# gerbang_f2.net
KiCad netlist of a schematic drawn in EAGLE
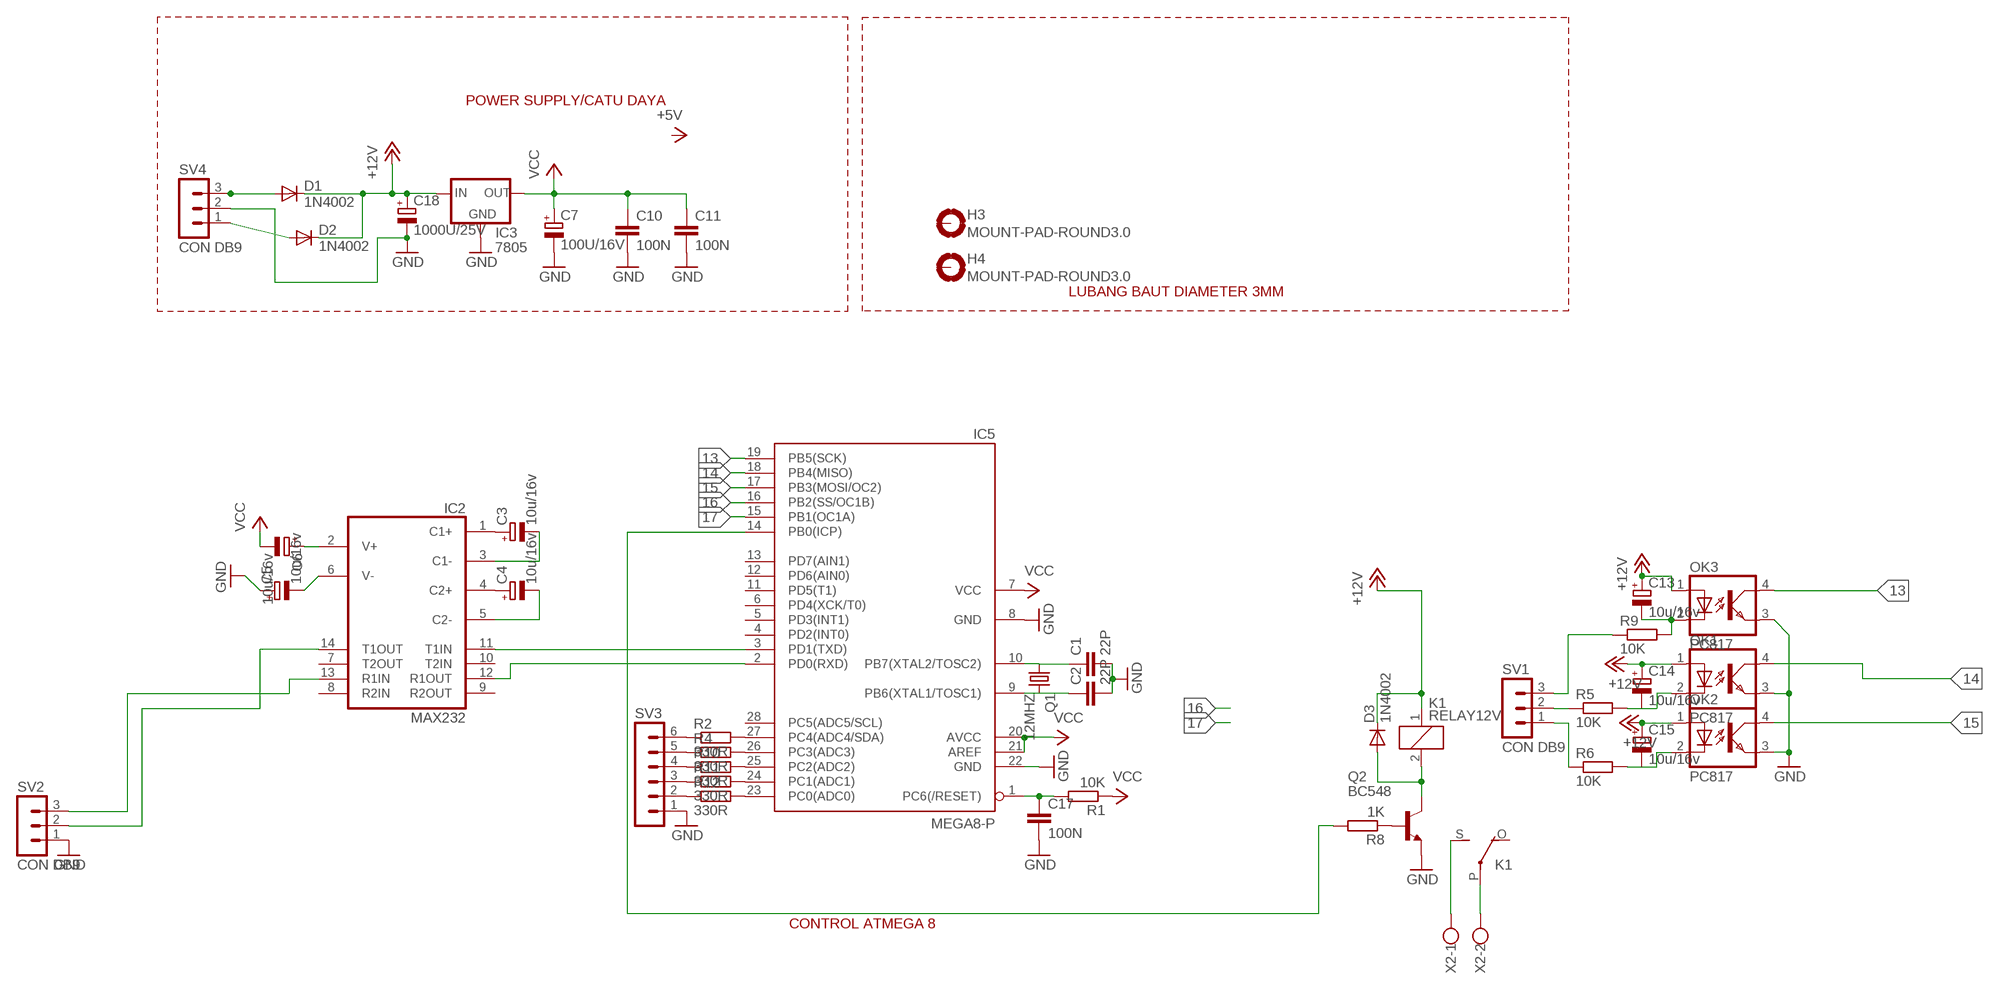
[diagram p0: schematic, sheet 1]

(export (version "E")
  (design (tool "Eeschema 10.0.6"))
  (components
    (comp (ref "C1")
      (value "22P")
      (footprint "eagle-import:C025-025X050")
      (libsource (lib "eagle-import") (part "C-EU025-025X050"))
    )
    (comp (ref "C2")
      (value "22P")
      (footprint "eagle-import:C025-025X050")
      (libsource (lib "eagle-import") (part "C-EU025-025X050"))
    )
    (comp (ref "C3")
      (value "10u/16v")
      (footprint "eagle-import:E2,5-6")
      (libsource (lib "eagle-import") (part "resistor_CPOL-EUE2.5-6"))
    )
    (comp (ref "C4")
      (value "10u/16v")
      (footprint "eagle-import:E2,5-6")
      (libsource (lib "eagle-import") (part "resistor_CPOL-EUE2.5-6"))
    )
    (comp (ref "C5")
      (value "10u/16v")
      (footprint "eagle-import:E2,5-6")
      (libsource (lib "eagle-import") (part "resistor_CPOL-EUE2.5-6"))
    )
    (comp (ref "C6")
      (value "10u/16v")
      (footprint "eagle-import:E2,5-6")
      (libsource (lib "eagle-import") (part "resistor_CPOL-EUE2.5-6"))
    )
    (comp (ref "C7")
      (value "100U/16V")
      (footprint "eagle-import:E2,5-6")
      (libsource (lib "eagle-import") (part "resistor_CPOL-EUE2.5-6"))
    )
    (comp (ref "C10")
      (value "100N")
      (footprint "eagle-import:C025-025X050")
      (libsource (lib "eagle-import") (part "C-EU025-025X050"))
    )
    (comp (ref "C11")
      (value "100N")
      (footprint "eagle-import:C025-025X050")
      (libsource (lib "eagle-import") (part "C-EU025-025X050"))
    )
    (comp (ref "C13")
      (value "10u/16v")
      (footprint "eagle-import:E2,5-6")
      (libsource (lib "eagle-import") (part "resistor_CPOL-EUE2.5-6"))
    )
    (comp (ref "C14")
      (value "10u/16v")
      (footprint "eagle-import:E2,5-6")
      (libsource (lib "eagle-import") (part "resistor_CPOL-EUE2.5-6"))
    )
    (comp (ref "C15")
      (value "10u/16v")
      (footprint "eagle-import:E2,5-6")
      (libsource (lib "eagle-import") (part "resistor_CPOL-EUE2.5-6"))
    )
    (comp (ref "C17")
      (value "100N")
      (footprint "eagle-import:C025-025X050")
      (libsource (lib "eagle-import") (part "C-EU025-025X050"))
    )
    (comp (ref "C18")
      (value "1000U/25V")
      (footprint "eagle-import:E5-8,5")
      (libsource (lib "eagle-import") (part "CPOL-EUE5-8.5"))
    )
    (comp (ref "D1")
      (value "1N4002")
      (footprint "eagle-import:DO35-10")
      (libsource (lib "eagle-import") (part "1N4148DO35-10"))
    )
    (comp (ref "D2")
      (value "1N4002")
      (footprint "eagle-import:DO35-10")
      (libsource (lib "eagle-import") (part "1N4148DO35-10"))
    )
    (comp (ref "D3")
      (value "1N4002")
      (footprint "eagle-import:DO35-10")
      (libsource (lib "eagle-import") (part "1N4148DO35-10"))
    )
    (comp (ref "H3")
      (value "MOUNT-PAD-ROUND3.0")
      (footprint "eagle-import:3,0-PAD")
      (libsource (lib "eagle-import") (part "MOUNT-PAD-ROUND3.0"))
    )
    (comp (ref "H4")
      (value "MOUNT-PAD-ROUND3.0")
      (footprint "eagle-import:3,0-PAD")
      (libsource (lib "eagle-import") (part "MOUNT-PAD-ROUND3.0"))
    )
    (comp (ref "IC2")
      (value "MAX232")
      (footprint "eagle-import:DIL16")
      (fields (field (name "MF") "MAXIM") (field (name "MPN") "MAX232ACPE+"))
      (libsource (lib "eagle-import") (part "MAX232"))
    )
    (comp (ref "IC3")
      (value "7805")
      (footprint "eagle-import:78XXS")
      (libsource (lib "eagle-import") (part "78XXS"))
    )
    (comp (ref "IC5")
      (value "MEGA8-P")
      (footprint "eagle-import:DIL28-3")
      (libsource (lib "eagle-import") (part "MEGA8-P"))
    )
    (comp (ref "K1")
      (value "RELAY12V")
      (footprint "eagle-import:ZF112")
      (libsource (lib "eagle-import") (part "ZF112"))
    )
    (comp (ref "OK1")
      (value "PC817")
      (footprint "eagle-import:DIL04")
      (fields (field (name "MPN") "PC817X4J000F"))
      (libsource (lib "eagle-import") (part "PC817"))
    )
    (comp (ref "OK2")
      (value "PC817")
      (footprint "eagle-import:DIL04")
      (fields (field (name "MPN") "PC817X4J000F"))
      (libsource (lib "eagle-import") (part "PC817"))
    )
    (comp (ref "OK3")
      (value "PC817")
      (footprint "eagle-import:DIL04")
      (fields (field (name "MPN") "PC817X4J000F"))
      (libsource (lib "eagle-import") (part "PC817"))
    )
    (comp (ref "Q1")
      (value "12MHZ")
      (footprint "eagle-import:HC49U-V")
      (libsource (lib "eagle-import") (part "CRYSTALHC49U-V"))
    )
    (comp (ref "Q2")
      (value "BC548")
      (footprint "eagle-import:TO92-EBC")
      (libsource (lib "eagle-import") (part "BC548"))
    )
    (comp (ref "R1")
      (value "10K")
      (footprint "eagle-import:0207_10")
      (libsource (lib "eagle-import") (part "resistor_R-EU_0207/10"))
    )
    (comp (ref "R2")
      (value "330R")
      (footprint "eagle-import:0204V")
      (libsource (lib "eagle-import") (part "R-EU_0204/2V"))
    )
    (comp (ref "R4")
      (value "330R")
      (footprint "eagle-import:0204V")
      (libsource (lib "eagle-import") (part "R-EU_0204/2V"))
    )
    (comp (ref "R5")
      (value "10K")
      (footprint "eagle-import:0204V")
      (libsource (lib "eagle-import") (part "R-EU_0204/2V"))
    )
    (comp (ref "R6")
      (value "10K")
      (footprint "eagle-import:0204V")
      (libsource (lib "eagle-import") (part "R-EU_0204/2V"))
    )
    (comp (ref "R8")
      (value "1K")
      (footprint "eagle-import:0207_10")
      (libsource (lib "eagle-import") (part "resistor_R-EU_0207/10"))
    )
    (comp (ref "R9")
      (value "10K")
      (footprint "eagle-import:0204V")
      (libsource (lib "eagle-import") (part "R-EU_0204/2V"))
    )
    (comp (ref "R10")
      (value "330R")
      (footprint "eagle-import:0204V")
      (libsource (lib "eagle-import") (part "R-EU_0204/2V"))
    )
    (comp (ref "R11")
      (value "330R")
      (footprint "eagle-import:0204V")
      (libsource (lib "eagle-import") (part "R-EU_0204/2V"))
    )
    (comp (ref "R12")
      (value "330R")
      (footprint "eagle-import:0204V")
      (libsource (lib "eagle-import") (part "R-EU_0204/2V"))
    )
    (comp (ref "SV1")
      (value "CON DB9")
      (footprint "eagle-import:MA03-1")
      (libsource (lib "eagle-import") (part "MA03-1"))
    )
    (comp (ref "SV2")
      (value "CON DB9")
      (footprint "eagle-import:MA03-1")
      (libsource (lib "eagle-import") (part "MA03-1"))
    )
    (comp (ref "SV3")
      (value "MA06-1")
      (footprint "eagle-import:MA06-1")
      (libsource (lib "eagle-import") (part "MA06-1"))
    )
    (comp (ref "SV4")
      (value "CON DB9")
      (footprint "eagle-import:MA03-1")
      (libsource (lib "eagle-import") (part "MA03-1"))
    )
    (comp (ref "X2")
      (value "W237-102")
      (footprint "eagle-import:W237-102")
      (fields (field (name "MPN") "237-102"))
      (libsource (lib "eagle-import") (part "W237-102"))
    )
  )
  (nets
    (net (code "2") (name "+12V") (class "Default")
      (node (ref "C13") (pin "+") (pinfunction "+_+") (pintype "passive"))
      (node (ref "C14") (pin "+") (pinfunction "+_+") (pintype "passive"))
      (node (ref "C15") (pin "+") (pinfunction "+_+") (pintype "passive"))
      (node (ref "C18") (pin "+") (pinfunction "+_+") (pintype "passive"))
      (node (ref "D1") (pin "C") (pinfunction "C_C") (pintype "passive"))
      (node (ref "D2") (pin "C") (pinfunction "C_C") (pintype "passive"))
      (node (ref "D3") (pin "C") (pinfunction "C_C") (pintype "passive"))
      (node (ref "IC3") (pin "IN") (pinfunction "IN_IN") (pintype "input"))
      (node (ref "K1") (pin "1") (pinfunction "1_1") (pintype "passive"))
      (node (ref "OK1") (pin "1") (pinfunction "A_1") (pintype "passive"))
      (node (ref "OK2") (pin "1") (pinfunction "A_1") (pintype "passive"))
      (node (ref "OK3") (pin "1") (pinfunction "A_1") (pintype "passive"))
    )
    (net (code "3") (name "13") (class "Default")
      (node (ref "IC5") (pin "19") (pinfunction "PB5(SCK)_19") (pintype "bidirectional"))
      (node (ref "OK3") (pin "4") (pinfunction "COL_4") (pintype "passive"))
    )
    (net (code "4") (name "14") (class "Default")
      (node (ref "IC5") (pin "18") (pinfunction "PB4(MISO)_18") (pintype "bidirectional"))
      (node (ref "OK1") (pin "4") (pinfunction "COL_4") (pintype "passive"))
    )
    (net (code "5") (name "15") (class "Default")
      (node (ref "IC5") (pin "17") (pinfunction "PB3(MOSI/OC2)_17") (pintype "bidirectional"))
      (node (ref "OK2") (pin "4") (pinfunction "COL_4") (pintype "passive"))
    )
    (net (code "6") (name "16") (class "Default")
      (node (ref "IC5") (pin "16") (pinfunction "PB2(SS/OC1B)_16") (pintype "bidirectional"))
    )
    (net (code "7") (name "17") (class "Default")
      (node (ref "IC5") (pin "15") (pinfunction "PB1(OC1A)_15") (pintype "bidirectional"))
    )
    (net (code "8") (name "GND") (class "Default")
      (node (ref "C1") (pin "2") (pinfunction "2_2") (pintype "passive"))
      (node (ref "C10") (pin "2") (pinfunction "2_2") (pintype "passive"))
      (node (ref "C11") (pin "2") (pinfunction "2_2") (pintype "passive"))
      (node (ref "C17") (pin "2") (pinfunction "2_2") (pintype "passive"))
      (node (ref "C18") (pin "-") (pinfunction "-_-") (pintype "passive"))
      (node (ref "C2") (pin "2") (pinfunction "2_2") (pintype "passive"))
      (node (ref "C5") (pin "+") (pinfunction "+_+") (pintype "passive"))
      (node (ref "C7") (pin "-") (pinfunction "-_-") (pintype "passive"))
      (node (ref "IC3") (pin "GND") (pinfunction "GND_GND") (pintype "input"))
      (node (ref "IC5") (pin "22") (pinfunction "GND_22") (pintype "power_in"))
      (node (ref "IC5") (pin "8") (pinfunction "GND_8") (pintype "power_in"))
      (node (ref "OK1") (pin "3") (pinfunction "EMIT_3") (pintype "passive"))
      (node (ref "OK2") (pin "3") (pinfunction "EMIT_3") (pintype "passive"))
      (node (ref "OK3") (pin "3") (pinfunction "EMIT_3") (pintype "passive"))
      (node (ref "Q2") (pin "E") (pinfunction "E_E") (pintype "passive"))
      (node (ref "SV2") (pin "1") (pinfunction "1_1") (pintype "passive"))
      (node (ref "SV3") (pin "1") (pinfunction "1_1") (pintype "passive"))
      (node (ref "SV4") (pin "2") (pinfunction "2_2") (pintype "passive"))
    )
    (net (code "9") (name "Net-(D1-PadA)") (class "Default")
      (node (ref "D1") (pin "A") (pinfunction "A_A") (pintype "passive"))
      (node (ref "SV4") (pin "3") (pinfunction "3_3") (pintype "passive"))
    )
    (net (code "10") (name "Net-(D2-PadA)") (class "Default")
      (node (ref "D2") (pin "A") (pinfunction "A_A") (pintype "passive"))
      (node (ref "SV4") (pin "1") (pinfunction "1_1") (pintype "passive"))
    )
    (net (code "11") (name "Net-(D3-PadA)") (class "Default")
      (node (ref "D3") (pin "A") (pinfunction "A_A") (pintype "passive"))
      (node (ref "K1") (pin "2") (pinfunction "2_2") (pintype "passive"))
      (node (ref "Q2") (pin "C") (pinfunction "C_C") (pintype "passive"))
    )
    (net (code "12") (name "Net-(IC2A-C1+)") (class "Default")
      (node (ref "C3") (pin "+") (pinfunction "+_+") (pintype "passive"))
      (node (ref "IC2") (pin "1") (pinfunction "C1+_1") (pintype "bidirectional"))
    )
    (net (code "13") (name "Net-(IC2A-C1-)") (class "Default")
      (node (ref "C3") (pin "-") (pinfunction "-_-") (pintype "passive"))
      (node (ref "IC2") (pin "3") (pinfunction "C1-_3") (pintype "bidirectional"))
    )
    (net (code "14") (name "Net-(IC2A-C2+)") (class "Default")
      (node (ref "C4") (pin "+") (pinfunction "+_+") (pintype "passive"))
      (node (ref "IC2") (pin "4") (pinfunction "C2+_4") (pintype "bidirectional"))
    )
    (net (code "15") (name "Net-(IC2A-C2-)") (class "Default")
      (node (ref "C4") (pin "-") (pinfunction "-_-") (pintype "passive"))
      (node (ref "IC2") (pin "5") (pinfunction "C2-_5") (pintype "bidirectional"))
    )
    (net (code "16") (name "Net-(IC2A-R1IN)") (class "Default")
      (node (ref "IC2") (pin "13") (pinfunction "R1IN_13") (pintype "input"))
      (node (ref "SV2") (pin "3") (pinfunction "3_3") (pintype "passive"))
    )
    (net (code "17") (name "Net-(IC2A-R1OUT)") (class "Default")
      (node (ref "IC2") (pin "12") (pinfunction "R1OUT_12") (pintype "output"))
      (node (ref "IC5") (pin "2") (pinfunction "PD0(RXD)_2") (pintype "bidirectional"))
    )
    (net (code "18") (name "Net-(IC2A-T1IN)") (class "Default")
      (node (ref "IC2") (pin "11") (pinfunction "T1IN_11") (pintype "input"))
      (node (ref "IC5") (pin "3") (pinfunction "PD1(TXD)_3") (pintype "bidirectional"))
    )
    (net (code "19") (name "Net-(IC2A-T1OUT)") (class "Default")
      (node (ref "IC2") (pin "14") (pinfunction "T1OUT_14") (pintype "output"))
      (node (ref "SV2") (pin "2") (pinfunction "2_2") (pintype "passive"))
    )
    (net (code "20") (name "Net-(IC2A-V+)") (class "Default")
      (node (ref "C6") (pin "+") (pinfunction "+_+") (pintype "passive"))
      (node (ref "IC2") (pin "2") (pinfunction "V+_2") (pintype "bidirectional"))
    )
    (net (code "21") (name "Net-(IC2A-V-)") (class "Default")
      (node (ref "C5") (pin "-") (pinfunction "-_-") (pintype "passive"))
      (node (ref "IC2") (pin "6") (pinfunction "V-_6") (pintype "bidirectional"))
    )
    (net (code "22") (name "Net-(IC5-PB0(ICP))") (class "Default")
      (node (ref "IC5") (pin "14") (pinfunction "PB0(ICP)_14") (pintype "bidirectional"))
      (node (ref "R8") (pin "2") (pinfunction "2_2") (pintype "passive"))
    )
    (net (code "23") (name "Net-(IC5-PB6(XTAL1{slash}TOSC1))") (class "Default")
      (node (ref "C2") (pin "1") (pinfunction "1_1") (pintype "passive"))
      (node (ref "IC5") (pin "9") (pinfunction "PB6(XTAL1/TOSC1)_9") (pintype "bidirectional"))
      (node (ref "Q1") (pin "2") (pinfunction "2_2") (pintype "passive"))
    )
    (net (code "24") (name "Net-(IC5-PB7(XTAL2{slash}TOSC2))") (class "Default")
      (node (ref "C1") (pin "1") (pinfunction "1_1") (pintype "passive"))
      (node (ref "IC5") (pin "10") (pinfunction "PB7(XTAL2/TOSC2)_10") (pintype "bidirectional"))
      (node (ref "Q1") (pin "1") (pinfunction "1_1") (pintype "passive"))
    )
    (net (code "25") (name "Net-(IC5-PC0(ADC0))") (class "Default")
      (node (ref "IC5") (pin "23") (pinfunction "PC0(ADC0)_23") (pintype "bidirectional"))
      (node (ref "R12") (pin "2") (pinfunction "2_2") (pintype "passive"))
    )
    (net (code "26") (name "Net-(IC5-PC1(ADC1))") (class "Default")
      (node (ref "IC5") (pin "24") (pinfunction "PC1(ADC1)_24") (pintype "bidirectional"))
      (node (ref "R11") (pin "2") (pinfunction "2_2") (pintype "passive"))
    )
    (net (code "27") (name "Net-(IC5-PC2(ADC2))") (class "Default")
      (node (ref "IC5") (pin "25") (pinfunction "PC2(ADC2)_25") (pintype "bidirectional"))
      (node (ref "R10") (pin "2") (pinfunction "2_2") (pintype "passive"))
    )
    (net (code "28") (name "Net-(IC5-PC3(ADC3))") (class "Default")
      (node (ref "IC5") (pin "26") (pinfunction "PC3(ADC3)_26") (pintype "bidirectional"))
      (node (ref "R4") (pin "2") (pinfunction "2_2") (pintype "passive"))
    )
    (net (code "29") (name "Net-(IC5-PC4(ADC4{slash}SDA))") (class "Default")
      (node (ref "IC5") (pin "27") (pinfunction "PC4(ADC4/SDA)_27") (pintype "bidirectional"))
      (node (ref "R2") (pin "2") (pinfunction "2_2") (pintype "passive"))
    )
    (net (code "30") (name "Net-(IC5-PC6({slash}RESET))") (class "Default")
      (node (ref "C17") (pin "1") (pinfunction "1_1") (pintype "passive"))
      (node (ref "IC5") (pin "1") (pinfunction "PC6(/RESET)_1") (pintype "bidirectional"))
      (node (ref "R1") (pin "2") (pinfunction "2_2") (pintype "passive"))
    )
    (net (code "31") (name "Net-(OK1-C)") (class "Default")
      (node (ref "C14") (pin "-") (pinfunction "-_-") (pintype "passive"))
      (node (ref "OK1") (pin "2") (pinfunction "C_2") (pintype "passive"))
      (node (ref "R5") (pin "2") (pinfunction "2_2") (pintype "passive"))
    )
    (net (code "32") (name "Net-(OK2-C)") (class "Default")
      (node (ref "C15") (pin "-") (pinfunction "-_-") (pintype "passive"))
      (node (ref "OK2") (pin "2") (pinfunction "C_2") (pintype "passive"))
      (node (ref "R6") (pin "2") (pinfunction "2_2") (pintype "passive"))
    )
    (net (code "33") (name "Net-(OK3-C)") (class "Default")
      (node (ref "C13") (pin "-") (pinfunction "-_-") (pintype "passive"))
      (node (ref "OK3") (pin "2") (pinfunction "C_2") (pintype "passive"))
      (node (ref "R9") (pin "2") (pinfunction "2_2") (pintype "passive"))
    )
    (net (code "34") (name "Net-(Q2-PadB)") (class "Default")
      (node (ref "Q2") (pin "B") (pinfunction "B_B") (pintype "passive"))
      (node (ref "R8") (pin "1") (pinfunction "1_1") (pintype "passive"))
    )
    (net (code "35") (name "Net-(R2-Pad1)") (class "Default")
      (node (ref "R2") (pin "1") (pinfunction "1_1") (pintype "passive"))
      (node (ref "SV3") (pin "6") (pinfunction "6_6") (pintype "passive"))
    )
    (net (code "36") (name "Net-(R4-Pad1)") (class "Default")
      (node (ref "R4") (pin "1") (pinfunction "1_1") (pintype "passive"))
      (node (ref "SV3") (pin "5") (pinfunction "5_5") (pintype "passive"))
    )
    (net (code "37") (name "Net-(R5-Pad1)") (class "Default")
      (node (ref "R5") (pin "1") (pinfunction "1_1") (pintype "passive"))
      (node (ref "SV1") (pin "2") (pinfunction "2_2") (pintype "passive"))
    )
    (net (code "38") (name "Net-(R6-Pad1)") (class "Default")
      (node (ref "R6") (pin "1") (pinfunction "1_1") (pintype "passive"))
      (node (ref "SV1") (pin "1") (pinfunction "1_1") (pintype "passive"))
    )
    (net (code "39") (name "Net-(R9-Pad1)") (class "Default")
      (node (ref "R9") (pin "1") (pinfunction "1_1") (pintype "passive"))
      (node (ref "SV1") (pin "3") (pinfunction "3_3") (pintype "passive"))
    )
    (net (code "40") (name "Net-(R10-Pad1)") (class "Default")
      (node (ref "R10") (pin "1") (pinfunction "1_1") (pintype "passive"))
      (node (ref "SV3") (pin "4") (pinfunction "4_4") (pintype "passive"))
    )
    (net (code "41") (name "Net-(R11-Pad1)") (class "Default")
      (node (ref "R11") (pin "1") (pinfunction "1_1") (pintype "passive"))
      (node (ref "SV3") (pin "3") (pinfunction "3_3") (pintype "passive"))
    )
    (net (code "42") (name "Net-(R12-Pad1)") (class "Default")
      (node (ref "R12") (pin "1") (pinfunction "1_1") (pintype "passive"))
      (node (ref "SV3") (pin "2") (pinfunction "2_2") (pintype "passive"))
    )
    (net (code "43") (name "Net-(X2A-KL)") (class "Default")
      (node (ref "K1") (pin "S") (pinfunction "S_S") (pintype "passive"))
      (node (ref "X2") (pin "1") (pinfunction "KL_1") (pintype "passive"))
    )
    (net (code "44") (name "Net-(X2B-KL)") (class "Default")
      (node (ref "K1") (pin "P") (pinfunction "P_P") (pintype "passive"))
      (node (ref "X2") (pin "2") (pinfunction "KL_2") (pintype "passive"))
    )
    (net (code "45") (name "VCC") (class "Default")
      (node (ref "C10") (pin "1") (pinfunction "1_1") (pintype "passive"))
      (node (ref "C11") (pin "1") (pinfunction "1_1") (pintype "passive"))
      (node (ref "C6") (pin "-") (pinfunction "-_-") (pintype "passive"))
      (node (ref "C7") (pin "+") (pinfunction "+_+") (pintype "passive"))
      (node (ref "IC3") (pin "OUT") (pinfunction "OUT_OUT") (pintype "passive"))
      (node (ref "IC5") (pin "20") (pinfunction "AVCC_20") (pintype "power_in"))
      (node (ref "IC5") (pin "21") (pinfunction "AREF_21") (pintype "passive"))
      (node (ref "IC5") (pin "7") (pinfunction "VCC_7") (pintype "power_in"))
      (node (ref "R1") (pin "1") (pinfunction "1_1") (pintype "passive"))
    )
    (net (code "46") (name "unconnected-(H3-MOUNT-PadB3,0)") (class "Default")
      (node (ref "H3") (pin "B3,0") (pinfunction "MOUNT_B3,0") (pintype "passive"))
    )
    (net (code "47") (name "unconnected-(H4-MOUNT-PadB3,0)") (class "Default")
      (node (ref "H4") (pin "B3,0") (pinfunction "MOUNT_B3,0") (pintype "passive"))
    )
    (net (code "48") (name "unconnected-(IC2A-R2IN-Pad8)") (class "Default")
      (node (ref "IC2") (pin "8") (pinfunction "R2IN_8") (pintype "input"))
    )
    (net (code "49") (name "unconnected-(IC2A-R2OUT-Pad9)") (class "Default")
      (node (ref "IC2") (pin "9") (pinfunction "R2OUT_9") (pintype "output"))
    )
    (net (code "50") (name "unconnected-(IC2A-T2IN-Pad10)") (class "Default")
      (node (ref "IC2") (pin "10") (pinfunction "T2IN_10") (pintype "input"))
    )
    (net (code "51") (name "unconnected-(IC2A-T2OUT-Pad7)") (class "Default")
      (node (ref "IC2") (pin "7") (pinfunction "T2OUT_7") (pintype "output"))
    )
    (net (code "52") (name "unconnected-(IC5-PC5(ADC5{slash}SCL)-Pad28)") (class "Default")
      (node (ref "IC5") (pin "28") (pinfunction "PC5(ADC5/SCL)_28") (pintype "bidirectional"))
    )
    (net (code "53") (name "unconnected-(IC5-PD2(INT0)-Pad4)") (class "Default")
      (node (ref "IC5") (pin "4") (pinfunction "PD2(INT0)_4") (pintype "bidirectional"))
    )
    (net (code "54") (name "unconnected-(IC5-PD3(INT1)-Pad5)") (class "Default")
      (node (ref "IC5") (pin "5") (pinfunction "PD3(INT1)_5") (pintype "bidirectional"))
    )
    (net (code "55") (name "unconnected-(IC5-PD4(XCK{slash}T0)-Pad6)") (class "Default")
      (node (ref "IC5") (pin "6") (pinfunction "PD4(XCK/T0)_6") (pintype "bidirectional"))
    )
    (net (code "56") (name "unconnected-(IC5-PD5(T1)-Pad11)") (class "Default")
      (node (ref "IC5") (pin "11") (pinfunction "PD5(T1)_11") (pintype "bidirectional"))
    )
    (net (code "57") (name "unconnected-(IC5-PD6(AIN0)-Pad12)") (class "Default")
      (node (ref "IC5") (pin "12") (pinfunction "PD6(AIN0)_12") (pintype "bidirectional"))
    )
    (net (code "58") (name "unconnected-(IC5-PD7(AIN1)-Pad13)") (class "Default")
      (node (ref "IC5") (pin "13") (pinfunction "PD7(AIN1)_13") (pintype "bidirectional"))
    )
    (net (code "59") (name "unconnected-(K1-PadO)") (class "Default")
      (node (ref "K1") (pin "O") (pinfunction "O_O") (pintype "passive"))
    )
  )
)
